# LED_Monitor.net
KiCad netlist of a schematic drawn in Altium Designer
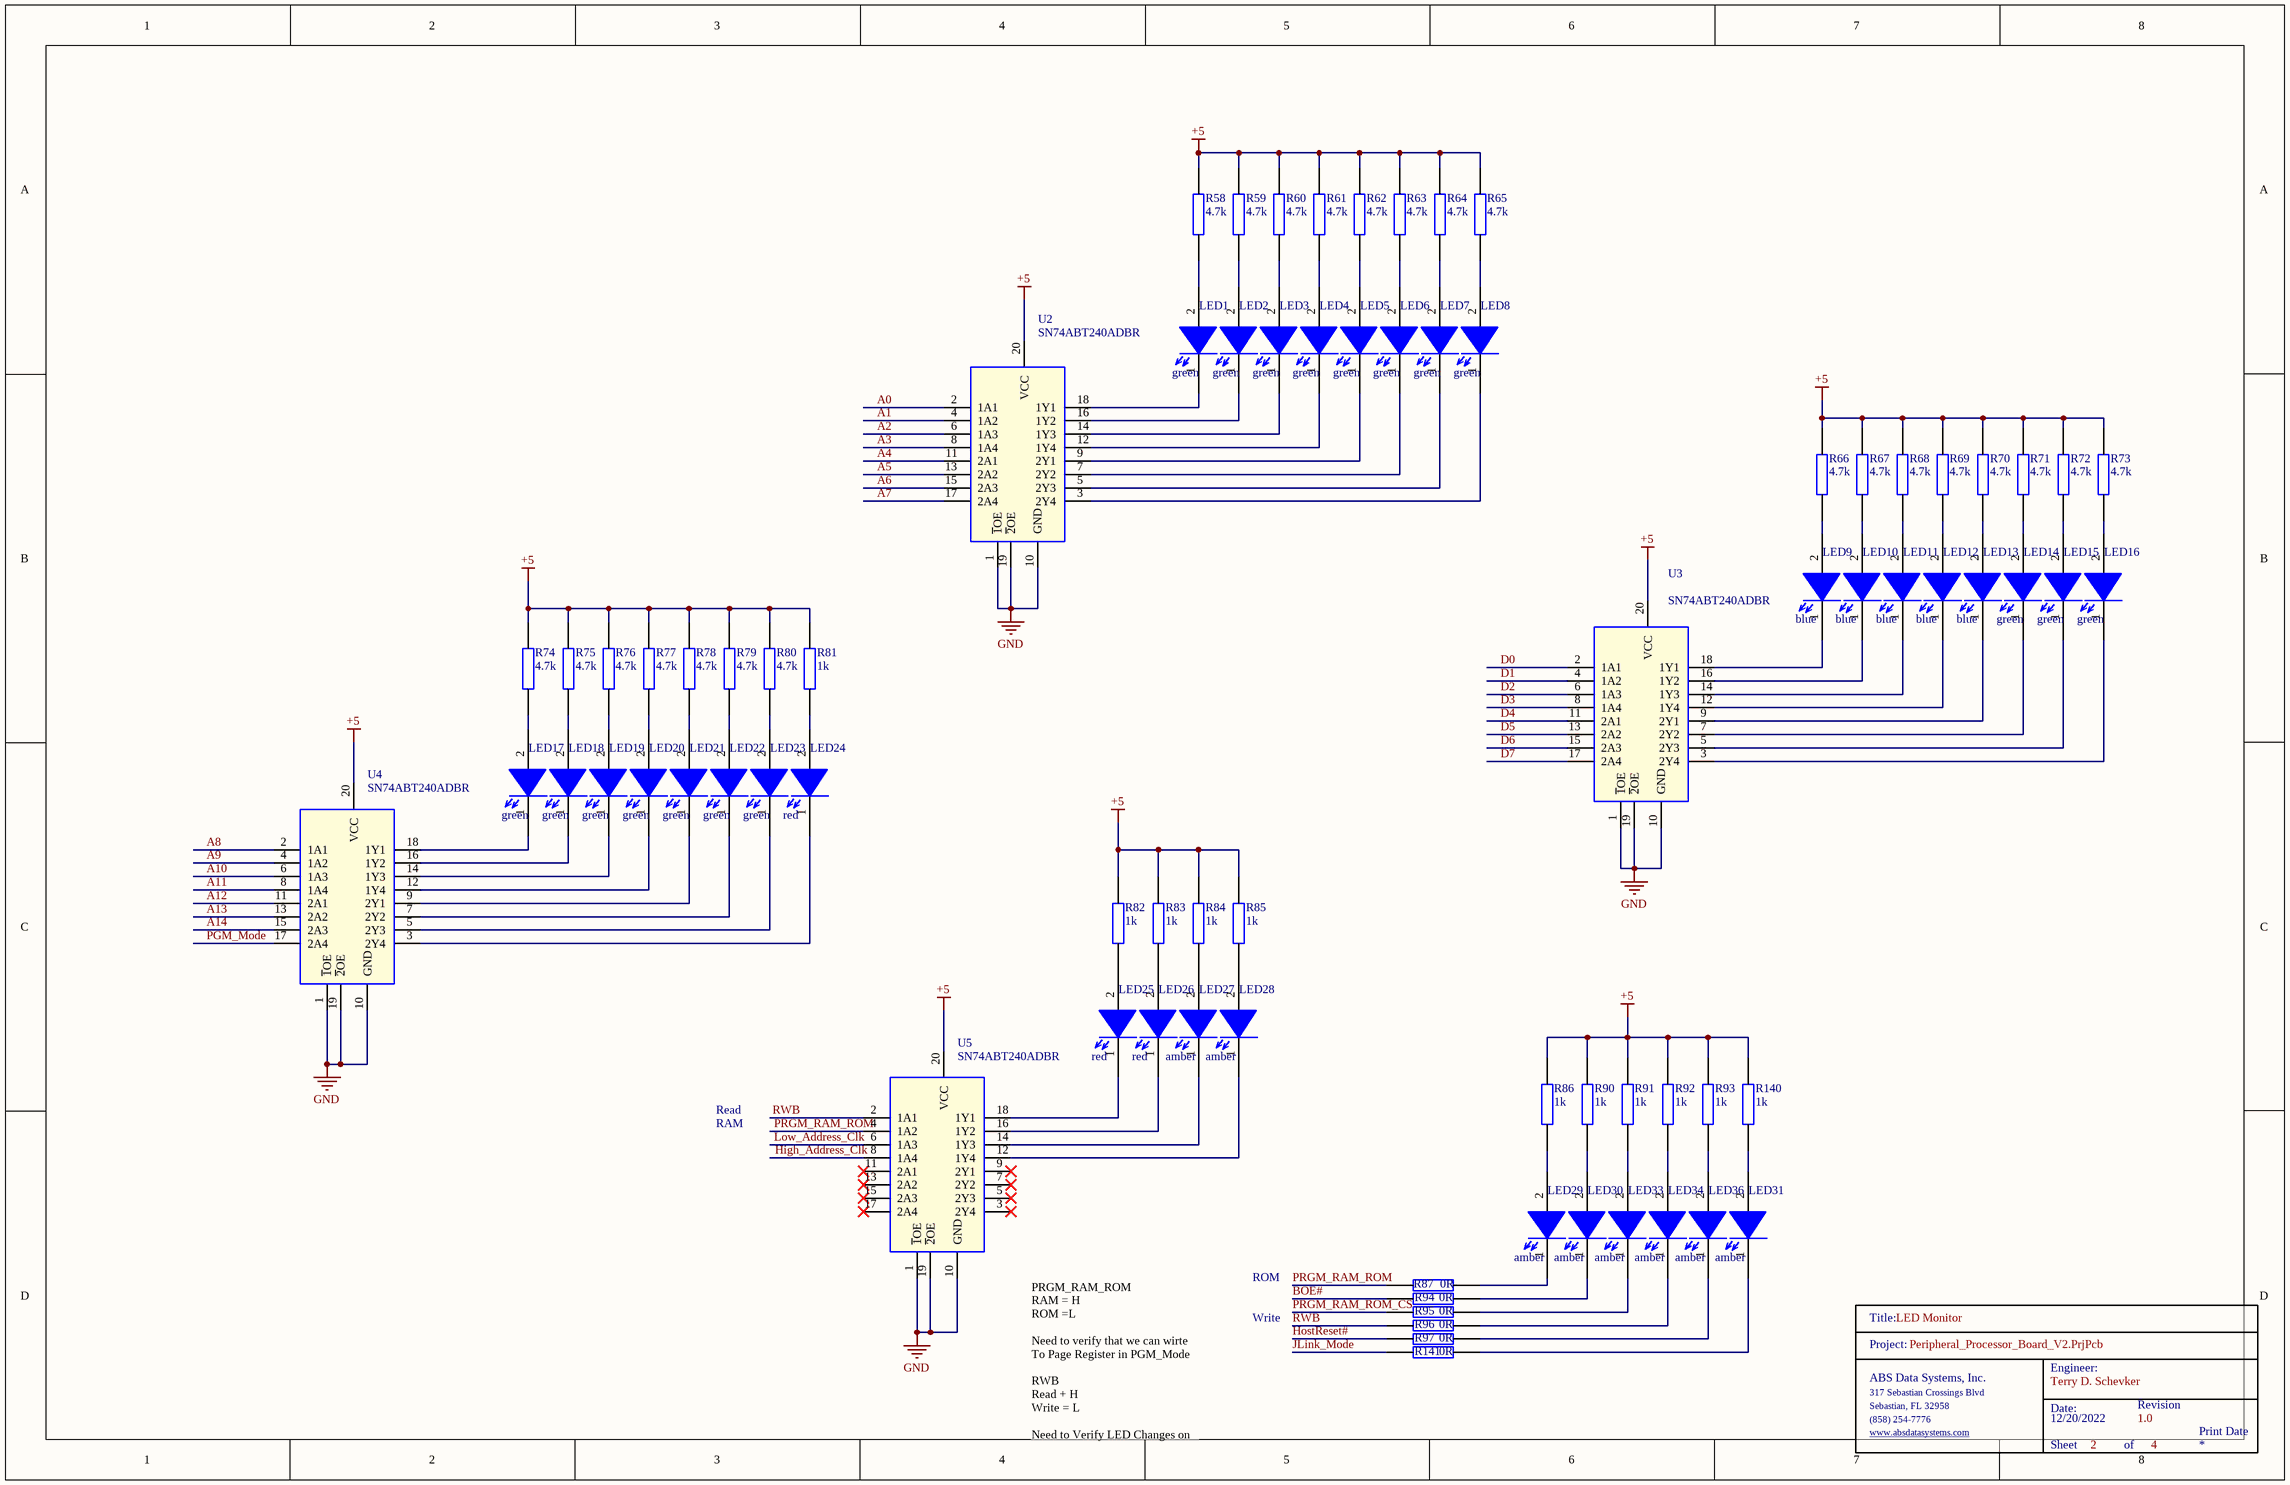
[diagram p0: LED_Monitor.SchDoc]

(export (version "E")
  (design (tool "Eeschema 10.0.6"))
  (components
    (comp (ref "LED1")
      (value "green")
      (footprint "0603_Diode")
      (description "Wurth Elektronik 0603 green")
      (fields
        (field (name "MANUFACTURER") "Wurth Electronics")
        (field (name "MANUFACTURER PART NUMBER") "150060GS75000")
      )
      (libsource (lib "Misc") (part "150060GS75000"))
    )
    (comp (ref "LED2")
      (value "green")
      (footprint "0603_Diode")
      (description "Wurth Elektronik 0603 green")
      (fields
        (field (name "MANUFACTURER") "Wurth Electronics")
        (field (name "MANUFACTURER PART NUMBER") "150060GS75000")
      )
      (libsource (lib "Misc") (part "150060GS75000"))
    )
    (comp (ref "LED3")
      (value "green")
      (footprint "0603_Diode")
      (description "Wurth Elektronik 0603 green")
      (fields
        (field (name "MANUFACTURER") "Wurth Electronics")
        (field (name "MANUFACTURER PART NUMBER") "150060GS75000")
      )
      (libsource (lib "Misc") (part "150060GS75000"))
    )
    (comp (ref "LED4")
      (value "green")
      (footprint "0603_Diode")
      (description "Wurth Elektronik 0603 green")
      (fields
        (field (name "MANUFACTURER") "Wurth Electronics")
        (field (name "MANUFACTURER PART NUMBER") "150060GS75000")
      )
      (libsource (lib "Misc") (part "150060GS75000"))
    )
    (comp (ref "LED5")
      (value "green")
      (footprint "0603_Diode")
      (description "Wurth Elektronik 0603 green")
      (fields
        (field (name "MANUFACTURER") "Wurth Electronics")
        (field (name "MANUFACTURER PART NUMBER") "150060GS75000")
      )
      (libsource (lib "Misc") (part "150060GS75000"))
    )
    (comp (ref "LED6")
      (value "green")
      (footprint "0603_Diode")
      (description "Wurth Elektronik 0603 green")
      (fields
        (field (name "MANUFACTURER") "Wurth Electronics")
        (field (name "MANUFACTURER PART NUMBER") "150060GS75000")
      )
      (libsource (lib "Misc") (part "150060GS75000"))
    )
    (comp (ref "LED7")
      (value "green")
      (footprint "0603_Diode")
      (description "Wurth Elektronik 0603 green")
      (fields
        (field (name "MANUFACTURER") "Wurth Electronics")
        (field (name "MANUFACTURER PART NUMBER") "150060GS75000")
      )
      (libsource (lib "Misc") (part "150060GS75000"))
    )
    (comp (ref "LED8")
      (value "green")
      (footprint "0603_Diode")
      (description "Wurth Elektronik 0603 green")
      (fields
        (field (name "MANUFACTURER") "Wurth Electronics")
        (field (name "MANUFACTURER PART NUMBER") "150060GS75000")
      )
      (libsource (lib "Misc") (part "150060GS75000"))
    )
    (comp (ref "LED9")
      (value "blue")
      (footprint "0603_Diode")
      (description "Wurth Elektronik 0603 blue")
      (fields
        (field (name "MANUFACTURER") "Wurth Electronics")
        (field (name "MANUFACTURER PART NUMBER") "150060GS75000")
      )
      (libsource (lib "Misc") (part "150060BS75000"))
    )
    (comp (ref "LED10")
      (value "blue")
      (footprint "0603_Diode")
      (description "Wurth Elektronik 0603 blue")
      (fields
        (field (name "MANUFACTURER") "Wurth Electronics")
        (field (name "MANUFACTURER PART NUMBER") "150060GS75000")
      )
      (libsource (lib "Misc") (part "150060BS75000"))
    )
    (comp (ref "LED11")
      (value "blue")
      (footprint "0603_Diode")
      (description "Wurth Elektronik 0603 blue")
      (fields
        (field (name "MANUFACTURER") "Wurth Electronics")
        (field (name "MANUFACTURER PART NUMBER") "150060GS75000")
      )
      (libsource (lib "Misc") (part "150060BS75000"))
    )
    (comp (ref "LED12")
      (value "blue")
      (footprint "0603_Diode")
      (description "Wurth Elektronik 0603 blue")
      (fields
        (field (name "MANUFACTURER") "Wurth Electronics")
        (field (name "MANUFACTURER PART NUMBER") "150060GS75000")
      )
      (libsource (lib "Misc") (part "150060BS75000"))
    )
    (comp (ref "LED13")
      (value "blue")
      (footprint "0603_Diode")
      (description "Wurth Elektronik 0603 blue")
      (fields
        (field (name "MANUFACTURER") "Wurth Electronics")
        (field (name "MANUFACTURER PART NUMBER") "150060GS75000")
      )
      (libsource (lib "Misc") (part "150060BS75000"))
    )
    (comp (ref "LED14")
      (value "green")
      (footprint "0603_Diode")
      (description "Wurth Elektronik 0603 green")
      (fields
        (field (name "MANUFACTURER") "Wurth Electronics")
        (field (name "MANUFACTURER PART NUMBER") "150060GS75000")
      )
      (libsource (lib "Misc") (part "150060GS75000"))
    )
    (comp (ref "LED15")
      (value "green")
      (footprint "0603_Diode")
      (description "Wurth Elektronik 0603 green")
      (fields
        (field (name "MANUFACTURER") "Wurth Electronics")
        (field (name "MANUFACTURER PART NUMBER") "150060GS75000")
      )
      (libsource (lib "Misc") (part "150060GS75000"))
    )
    (comp (ref "LED16")
      (value "green")
      (footprint "0603_Diode")
      (description "Wurth Elektronik 0603 green")
      (fields
        (field (name "MANUFACTURER") "Wurth Electronics")
        (field (name "MANUFACTURER PART NUMBER") "150060GS75000")
      )
      (libsource (lib "Misc") (part "150060GS75000"))
    )
    (comp (ref "LED17")
      (value "green")
      (footprint "0603_Diode")
      (description "Wurth Elektronik 0603 green")
      (fields
        (field (name "MANUFACTURER") "Wurth Electronics")
        (field (name "MANUFACTURER PART NUMBER") "150060GS75000")
      )
      (libsource (lib "Misc") (part "150060GS75000"))
    )
    (comp (ref "LED18")
      (value "green")
      (footprint "0603_Diode")
      (description "Wurth Elektronik 0603 green")
      (fields
        (field (name "MANUFACTURER") "Wurth Electronics")
        (field (name "MANUFACTURER PART NUMBER") "150060GS75000")
      )
      (libsource (lib "Misc") (part "150060GS75000"))
    )
    (comp (ref "LED19")
      (value "green")
      (footprint "0603_Diode")
      (description "Wurth Elektronik 0603 green")
      (fields
        (field (name "MANUFACTURER") "Wurth Electronics")
        (field (name "MANUFACTURER PART NUMBER") "150060GS75000")
      )
      (libsource (lib "Misc") (part "150060GS75000"))
    )
    (comp (ref "LED20")
      (value "green")
      (footprint "0603_Diode")
      (description "Wurth Elektronik 0603 green")
      (fields
        (field (name "MANUFACTURER") "Wurth Electronics")
        (field (name "MANUFACTURER PART NUMBER") "150060GS75000")
      )
      (libsource (lib "Misc") (part "150060GS75000"))
    )
    (comp (ref "LED21")
      (value "green")
      (footprint "0603_Diode")
      (description "Wurth Elektronik 0603 green")
      (fields
        (field (name "MANUFACTURER") "Wurth Electronics")
        (field (name "MANUFACTURER PART NUMBER") "150060GS75000")
      )
      (libsource (lib "Misc") (part "150060GS75000"))
    )
    (comp (ref "LED22")
      (value "green")
      (footprint "0603_Diode")
      (description "Wurth Elektronik 0603 green")
      (fields
        (field (name "MANUFACTURER") "Wurth Electronics")
        (field (name "MANUFACTURER PART NUMBER") "150060GS75000")
      )
      (libsource (lib "Misc") (part "150060GS75000"))
    )
    (comp (ref "LED23")
      (value "green")
      (footprint "0603_Diode")
      (description "Wurth Elektronik 0603 green")
      (fields
        (field (name "MANUFACTURER") "Wurth Electronics")
        (field (name "MANUFACTURER PART NUMBER") "150060GS75000")
      )
      (libsource (lib "Misc") (part "150060GS75000"))
    )
    (comp (ref "LED24")
      (value "red")
      (footprint "0603_Diode")
      (description "Wurth Elektronik 0603 red")
      (fields
        (field (name "MANUFACTURER") "Wurth Electronics")
        (field (name "MANUFACTURER PART NUMBER") "150060GS75000")
      )
      (libsource (lib "Misc") (part "150060RS75000"))
    )
    (comp (ref "LED25")
      (value "red")
      (footprint "0603_Diode")
      (description "Wurth Elektronik 0603 red")
      (fields
        (field (name "MANUFACTURER") "Wurth Electronics")
        (field (name "MANUFACTURER PART NUMBER") "150060GS75000")
      )
      (libsource (lib "Misc") (part "150060RS75000"))
    )
    (comp (ref "LED26")
      (value "red")
      (footprint "0603_Diode")
      (description "Wurth Elektronik 0603 red")
      (fields
        (field (name "MANUFACTURER") "Wurth Electronics")
        (field (name "MANUFACTURER PART NUMBER") "150060GS75000")
      )
      (libsource (lib "Misc") (part "150060RS75000"))
    )
    (comp (ref "LED27")
      (value "amber")
      (footprint "0603_Diode")
      (description "Wurth Elektronik 0603 amber")
      (fields
        (field (name "MANUFACTURER") "Wurth Electronics")
        (field (name "MANUFACTURER PART NUMBER") "150060GS75000")
      )
      (libsource (lib "Misc") (part "150060AS75000"))
    )
    (comp (ref "LED28")
      (value "amber")
      (footprint "0603_Diode")
      (description "Wurth Elektronik 0603 amber")
      (fields
        (field (name "MANUFACTURER") "Wurth Electronics")
        (field (name "MANUFACTURER PART NUMBER") "150060GS75000")
      )
      (libsource (lib "Misc") (part "150060AS75000"))
    )
    (comp (ref "LED29")
      (value "amber")
      (footprint "0603_Diode")
      (description "Wurth Elektronik 0603 amber")
      (fields
        (field (name "MANUFACTURER") "Wurth Electronics")
        (field (name "MANUFACTURER PART NUMBER") "150060GS75000")
      )
      (libsource (lib "Misc") (part "150060AS75000"))
    )
    (comp (ref "LED30")
      (value "amber")
      (footprint "0603_Diode")
      (description "Wurth Elektronik 0603 amber")
      (fields
        (field (name "MANUFACTURER") "Wurth Electronics")
        (field (name "MANUFACTURER PART NUMBER") "150060GS75000")
      )
      (libsource (lib "Misc") (part "150060AS75000"))
    )
    (comp (ref "LED31")
      (value "amber")
      (footprint "0603_Diode")
      (description "Wurth Elektronik 0603 amber")
      (fields
        (field (name "MANUFACTURER") "Wurth Electronics")
        (field (name "MANUFACTURER PART NUMBER") "150060GS75000")
      )
      (libsource (lib "Misc") (part "150060AS75000"))
    )
    (comp (ref "LED33")
      (value "amber")
      (footprint "0603_Diode")
      (description "Wurth Elektronik 0603 amber")
      (fields
        (field (name "MANUFACTURER") "Wurth Electronics")
        (field (name "MANUFACTURER PART NUMBER") "150060GS75000")
      )
      (libsource (lib "Misc") (part "150060AS75000"))
    )
    (comp (ref "LED34")
      (value "amber")
      (footprint "0603_Diode")
      (description "Wurth Elektronik 0603 amber")
      (fields
        (field (name "MANUFACTURER") "Wurth Electronics")
        (field (name "MANUFACTURER PART NUMBER") "150060GS75000")
      )
      (libsource (lib "Misc") (part "150060AS75000"))
    )
    (comp (ref "LED36")
      (value "amber")
      (footprint "0603_Diode")
      (description "Wurth Elektronik 0603 amber")
      (fields
        (field (name "MANUFACTURER") "Wurth Electronics")
        (field (name "MANUFACTURER PART NUMBER") "150060GS75000")
      )
      (libsource (lib "Misc") (part "150060AS75000"))
    )
    (comp (ref "R58")
      (value "4.7k")
      (footprint "0603")
      (description "YAGEO 0603 4.7k")
      (fields
        (field (name "MOUSER PART NUMBER") "603-RC0603JR-070RL")
        (field (name "MANUFACTURER_PART_NUMBER") "RC0603JR-070RL")
      )
      (libsource (lib "Resistors") (part "RC0603FR-104K7L"))
    )
    (comp (ref "R59")
      (value "4.7k")
      (footprint "0603")
      (description "YAGEO 0603 4.7k")
      (fields
        (field (name "MOUSER PART NUMBER") "603-RC0603JR-070RL")
        (field (name "MANUFACTURER_PART_NUMBER") "RC0603JR-070RL")
      )
      (libsource (lib "Resistors") (part "RC0603FR-104K7L"))
    )
    (comp (ref "R60")
      (value "4.7k")
      (footprint "0603")
      (description "YAGEO 0603 4.7k")
      (fields
        (field (name "MOUSER PART NUMBER") "603-RC0603JR-070RL")
        (field (name "MANUFACTURER_PART_NUMBER") "RC0603JR-070RL")
      )
      (libsource (lib "Resistors") (part "RC0603FR-104K7L"))
    )
    (comp (ref "R61")
      (value "4.7k")
      (footprint "0603")
      (description "YAGEO 0603 4.7k")
      (fields
        (field (name "MOUSER PART NUMBER") "603-RC0603JR-070RL")
        (field (name "MANUFACTURER_PART_NUMBER") "RC0603JR-070RL")
      )
      (libsource (lib "Resistors") (part "RC0603FR-104K7L"))
    )
    (comp (ref "R62")
      (value "4.7k")
      (footprint "0603")
      (description "YAGEO 0603 4.7k")
      (fields
        (field (name "MOUSER PART NUMBER") "603-RC0603JR-070RL")
        (field (name "MANUFACTURER_PART_NUMBER") "RC0603JR-070RL")
      )
      (libsource (lib "Resistors") (part "RC0603FR-104K7L"))
    )
    (comp (ref "R63")
      (value "4.7k")
      (footprint "0603")
      (description "YAGEO 0603 4.7k")
      (fields
        (field (name "MOUSER PART NUMBER") "603-RC0603JR-070RL")
        (field (name "MANUFACTURER_PART_NUMBER") "RC0603JR-070RL")
      )
      (libsource (lib "Resistors") (part "RC0603FR-104K7L"))
    )
    (comp (ref "R64")
      (value "4.7k")
      (footprint "0603")
      (description "YAGEO 0603 4.7k")
      (fields
        (field (name "MOUSER PART NUMBER") "603-RC0603JR-070RL")
        (field (name "MANUFACTURER_PART_NUMBER") "RC0603JR-070RL")
      )
      (libsource (lib "Resistors") (part "RC0603FR-104K7L"))
    )
    (comp (ref "R65")
      (value "4.7k")
      (footprint "0603")
      (description "YAGEO 0603 4.7k")
      (fields
        (field (name "MOUSER PART NUMBER") "603-RC0603JR-070RL")
        (field (name "MANUFACTURER_PART_NUMBER") "RC0603JR-070RL")
      )
      (libsource (lib "Resistors") (part "RC0603FR-104K7L"))
    )
    (comp (ref "R66")
      (value "4.7k")
      (footprint "0603")
      (description "YAGEO 0603 4.7k")
      (fields
        (field (name "MOUSER PART NUMBER") "603-RC0603JR-070RL")
        (field (name "MANUFACTURER_PART_NUMBER") "RC0603JR-070RL")
      )
      (libsource (lib "Resistors") (part "RC0603FR-104K7L"))
    )
    (comp (ref "R67")
      (value "4.7k")
      (footprint "0603")
      (description "YAGEO 0603 4.7k")
      (fields
        (field (name "MOUSER PART NUMBER") "603-RC0603JR-070RL")
        (field (name "MANUFACTURER_PART_NUMBER") "RC0603JR-070RL")
      )
      (libsource (lib "Resistors") (part "RC0603FR-104K7L"))
    )
    (comp (ref "R68")
      (value "4.7k")
      (footprint "0603")
      (description "YAGEO 0603 4.7k")
      (fields
        (field (name "MOUSER PART NUMBER") "603-RC0603JR-070RL")
        (field (name "MANUFACTURER_PART_NUMBER") "RC0603JR-070RL")
      )
      (libsource (lib "Resistors") (part "RC0603FR-104K7L"))
    )
    (comp (ref "R69")
      (value "4.7k")
      (footprint "0603")
      (description "YAGEO 0603 4.7k")
      (fields
        (field (name "MOUSER PART NUMBER") "603-RC0603JR-070RL")
        (field (name "MANUFACTURER_PART_NUMBER") "RC0603JR-070RL")
      )
      (libsource (lib "Resistors") (part "RC0603FR-104K7L"))
    )
    (comp (ref "R70")
      (value "4.7k")
      (footprint "0603")
      (description "YAGEO 0603 4.7k")
      (fields
        (field (name "MOUSER PART NUMBER") "603-RC0603JR-070RL")
        (field (name "MANUFACTURER_PART_NUMBER") "RC0603JR-070RL")
      )
      (libsource (lib "Resistors") (part "RC0603FR-104K7L"))
    )
    (comp (ref "R71")
      (value "4.7k")
      (footprint "0603")
      (description "YAGEO 0603 4.7k")
      (fields
        (field (name "MOUSER PART NUMBER") "603-RC0603JR-070RL")
        (field (name "MANUFACTURER_PART_NUMBER") "RC0603JR-070RL")
      )
      (libsource (lib "Resistors") (part "RC0603FR-104K7L"))
    )
    (comp (ref "R72")
      (value "4.7k")
      (footprint "0603")
      (description "YAGEO 0603 4.7k")
      (fields
        (field (name "MOUSER PART NUMBER") "603-RC0603JR-070RL")
        (field (name "MANUFACTURER_PART_NUMBER") "RC0603JR-070RL")
      )
      (libsource (lib "Resistors") (part "RC0603FR-104K7L"))
    )
    (comp (ref "R73")
      (value "4.7k")
      (footprint "0603")
      (description "YAGEO 0603 4.7k")
      (fields
        (field (name "MOUSER PART NUMBER") "603-RC0603JR-070RL")
        (field (name "MANUFACTURER_PART_NUMBER") "RC0603JR-070RL")
      )
      (libsource (lib "Resistors") (part "RC0603FR-104K7L"))
    )
    (comp (ref "R74")
      (value "4.7k")
      (footprint "0603")
      (description "YAGEO 0603 4.7k")
      (fields
        (field (name "MOUSER PART NUMBER") "603-RC0603JR-070RL")
        (field (name "MANUFACTURER_PART_NUMBER") "RC0603JR-070RL")
      )
      (libsource (lib "Resistors") (part "RC0603FR-104K7L"))
    )
    (comp (ref "R75")
      (value "4.7k")
      (footprint "0603")
      (description "YAGEO 0603 4.7k")
      (fields
        (field (name "MOUSER PART NUMBER") "603-RC0603JR-070RL")
        (field (name "MANUFACTURER_PART_NUMBER") "RC0603JR-070RL")
      )
      (libsource (lib "Resistors") (part "RC0603FR-104K7L"))
    )
    (comp (ref "R76")
      (value "4.7k")
      (footprint "0603")
      (description "YAGEO 0603 4.7k")
      (fields
        (field (name "MOUSER PART NUMBER") "603-RC0603JR-070RL")
        (field (name "MANUFACTURER_PART_NUMBER") "RC0603JR-070RL")
      )
      (libsource (lib "Resistors") (part "RC0603FR-104K7L"))
    )
    (comp (ref "R77")
      (value "4.7k")
      (footprint "0603")
      (description "YAGEO 0603 4.7k")
      (fields
        (field (name "MOUSER PART NUMBER") "603-RC0603JR-070RL")
        (field (name "MANUFACTURER_PART_NUMBER") "RC0603JR-070RL")
      )
      (libsource (lib "Resistors") (part "RC0603FR-104K7L"))
    )
    (comp (ref "R78")
      (value "4.7k")
      (footprint "0603")
      (description "YAGEO 0603 4.7k")
      (fields
        (field (name "MOUSER PART NUMBER") "603-RC0603JR-070RL")
        (field (name "MANUFACTURER_PART_NUMBER") "RC0603JR-070RL")
      )
      (libsource (lib "Resistors") (part "RC0603FR-104K7L"))
    )
    (comp (ref "R79")
      (value "4.7k")
      (footprint "0603")
      (description "YAGEO 0603 4.7k")
      (fields
        (field (name "MOUSER PART NUMBER") "603-RC0603JR-070RL")
        (field (name "MANUFACTURER_PART_NUMBER") "RC0603JR-070RL")
      )
      (libsource (lib "Resistors") (part "RC0603FR-104K7L"))
    )
    (comp (ref "R80")
      (value "4.7k")
      (footprint "0603")
      (description "YAGEO 0603 4.7k")
      (fields
        (field (name "MOUSER PART NUMBER") "603-RC0603JR-070RL")
        (field (name "MANUFACTURER_PART_NUMBER") "RC0603JR-070RL")
      )
      (libsource (lib "Resistors") (part "RC0603FR-104K7L"))
    )
    (comp (ref "R81")
      (value "1k")
      (footprint "0603")
      (description "YAGEO 0603 1k ohm")
      (fields
        (field (name "MOUSER PART NUMBER") "603-RC0603JR-070RL")
        (field (name "MANUFACTURER_PART_NUMBER") "RC0603JR-070RL")
      )
      (libsource (lib "Resistors") (part "AC0603FR-7W1KL_1"))
    )
    (comp (ref "R82")
      (value "1k")
      (footprint "0603")
      (description "YAGEO 0603 1k ohm")
      (fields
        (field (name "MOUSER PART NUMBER") "603-RC0603JR-070RL")
        (field (name "MANUFACTURER_PART_NUMBER") "RC0603JR-070RL")
      )
      (libsource (lib "Resistors") (part "AC0603FR-7W1KL_1"))
    )
    (comp (ref "R83")
      (value "1k")
      (footprint "0603")
      (description "YAGEO 0603 1k ohm")
      (fields
        (field (name "MOUSER PART NUMBER") "603-RC0603JR-070RL")
        (field (name "MANUFACTURER_PART_NUMBER") "RC0603JR-070RL")
      )
      (libsource (lib "Resistors") (part "AC0603FR-7W1KL_1"))
    )
    (comp (ref "R84")
      (value "1k")
      (footprint "0603")
      (description "YAGEO 0603 1k ohm")
      (fields
        (field (name "MOUSER PART NUMBER") "603-RC0603JR-070RL")
        (field (name "MANUFACTURER_PART_NUMBER") "RC0603JR-070RL")
      )
      (libsource (lib "Resistors") (part "AC0603FR-7W1KL_1"))
    )
    (comp (ref "R85")
      (value "1k")
      (footprint "0603")
      (description "YAGEO 0603 1k ohm")
      (fields
        (field (name "MOUSER PART NUMBER") "603-RC0603JR-070RL")
        (field (name "MANUFACTURER_PART_NUMBER") "RC0603JR-070RL")
      )
      (libsource (lib "Resistors") (part "AC0603FR-7W1KL_1"))
    )
    (comp (ref "R86")
      (value "1k")
      (footprint "0603")
      (description "YAGEO 0603 1k ohm")
      (fields
        (field (name "MOUSER PART NUMBER") "603-RC0603JR-070RL")
        (field (name "MANUFACTURER_PART_NUMBER") "RC0603JR-070RL")
      )
      (libsource (lib "Resistors") (part "AC0603FR-7W1KL_1"))
    )
    (comp (ref "R87")
      (value "0R")
      (footprint "0603")
      (description "YAGEO 0603 0 ohm")
      (fields
        (field (name "MOUSER PART NUMBER") "603-RC0603JR-070RL")
        (field (name "MANUFACTURER_PART_NUMBER") "RC0603JR-070RL")
      )
      (libsource (lib "Resistors") (part "RC0603JR-070RL"))
    )
    (comp (ref "R90")
      (value "1k")
      (footprint "0603")
      (description "YAGEO 0603 1k ohm")
      (fields
        (field (name "MOUSER PART NUMBER") "603-RC0603JR-070RL")
        (field (name "MANUFACTURER_PART_NUMBER") "RC0603JR-070RL")
      )
      (libsource (lib "Resistors") (part "AC0603FR-7W1KL_1"))
    )
    (comp (ref "R91")
      (value "1k")
      (footprint "0603")
      (description "YAGEO 0603 1k ohm")
      (fields
        (field (name "MOUSER PART NUMBER") "603-RC0603JR-070RL")
        (field (name "MANUFACTURER_PART_NUMBER") "RC0603JR-070RL")
      )
      (libsource (lib "Resistors") (part "AC0603FR-7W1KL_1"))
    )
    (comp (ref "R92")
      (value "1k")
      (footprint "0603")
      (description "YAGEO 0603 1k ohm")
      (fields
        (field (name "MOUSER PART NUMBER") "603-RC0603JR-070RL")
        (field (name "MANUFACTURER_PART_NUMBER") "RC0603JR-070RL")
      )
      (libsource (lib "Resistors") (part "AC0603FR-7W1KL_1"))
    )
    (comp (ref "R93")
      (value "1k")
      (footprint "0603")
      (description "YAGEO 0603 1k ohm")
      (fields
        (field (name "MOUSER PART NUMBER") "603-RC0603JR-070RL")
        (field (name "MANUFACTURER_PART_NUMBER") "RC0603JR-070RL")
      )
      (libsource (lib "Resistors") (part "AC0603FR-7W1KL_1"))
    )
    (comp (ref "R94")
      (value "0R")
      (footprint "0603")
      (description "YAGEO 0603 0 ohm")
      (fields
        (field (name "MOUSER PART NUMBER") "603-RC0603JR-070RL")
        (field (name "MANUFACTURER_PART_NUMBER") "RC0603JR-070RL")
      )
      (libsource (lib "Resistors") (part "RC0603JR-070RL"))
    )
    (comp (ref "R95")
      (value "0R")
      (footprint "0603")
      (description "YAGEO 0603 0 ohm")
      (fields
        (field (name "MOUSER PART NUMBER") "603-RC0603JR-070RL")
        (field (name "MANUFACTURER_PART_NUMBER") "RC0603JR-070RL")
      )
      (libsource (lib "Resistors") (part "RC0603JR-070RL"))
    )
    (comp (ref "R96")
      (value "0R")
      (footprint "0603")
      (description "YAGEO 0603 0 ohm")
      (fields
        (field (name "MOUSER PART NUMBER") "603-RC0603JR-070RL")
        (field (name "MANUFACTURER_PART_NUMBER") "RC0603JR-070RL")
      )
      (libsource (lib "Resistors") (part "RC0603JR-070RL"))
    )
    (comp (ref "R97")
      (value "0R")
      (footprint "0603")
      (description "YAGEO 0603 0 ohm")
      (fields
        (field (name "MOUSER PART NUMBER") "603-RC0603JR-070RL")
        (field (name "MANUFACTURER_PART_NUMBER") "RC0603JR-070RL")
      )
      (libsource (lib "Resistors") (part "RC0603JR-070RL"))
    )
    (comp (ref "R140")
      (value "1k")
      (footprint "Resistors:0603")
      (description "YAGEO 0603 1k ohm")
      (fields
        (field (name "MOUSER PART NUMBER") "603-RC0603JR-070RL")
        (field (name "MANUFACTURER_PART_NUMBER") "RC0603JR-070RL")
      )
      (libsource (lib "Resistors") (part "AC0603FR-7W1KL_1"))
    )
    (comp (ref "R141")
      (value "0R")
      (footprint "Resistors:0603")
      (description "YAGEO 0603 0 ohm")
      (fields
        (field (name "MOUSER PART NUMBER") "603-RC0603JR-070RL")
        (field (name "MANUFACTURER_PART_NUMBER") "RC0603JR-070RL")
      )
      (libsource (lib "Resistors") (part "RC0603JR-070RL"))
    )
    (comp (ref "TitleBlock_1") (value "TitleBlock") (libsource (lib "Misc") (part "TitleBlock")))
    (comp (ref "U2")
      (value "SN74ABT240ADBR")
      (footprint "SOP65P780X200-20N")
      (description "Octal Buffers/Drivers With 3-State Outputs")
      (fields (field (name "MOUSER PART NUMBER") "595-SN74ABT240ADBR"))
      (libsource (lib "Logic") (part "SN74ABT240ADBR"))
    )
    (comp (ref "U3")
      (value "SN74ABT240ADBR")
      (footprint "SOP65P780X200-20N")
      (description "Octal Buffers/Drivers With 3-State Outputs")
      (fields (field (name "MOUSER PART NUMBER") "595-SN74ABT240ADBR"))
      (libsource (lib "Logic") (part "SN74ABT240ADBR"))
    )
    (comp (ref "U4")
      (value "SN74ABT240ADBR")
      (footprint "SOP65P780X200-20N")
      (description "Octal Buffers/Drivers With 3-State Outputs")
      (fields (field (name "MOUSER PART NUMBER") "595-SN74ABT240ADBR"))
      (libsource (lib "Logic") (part "SN74ABT240ADBR"))
    )
    (comp (ref "U5")
      (value "SN74ABT240ADBR")
      (footprint "SOP65P780X200-20N")
      (description "Octal Buffers/Drivers With 3-State Outputs")
      (fields (field (name "MOUSER PART NUMBER") "595-SN74ABT240ADBR"))
      (libsource (lib "Logic") (part "SN74ABT240ADBR"))
    )
  )
  (nets
    (net (code "1") (name "+5") (class "Default")
      (node (ref "R140") (pin "2") (pinfunction "2_2") (pintype "passive"))
      (node (ref "R58") (pin "2") (pinfunction "2_2") (pintype "passive"))
      (node (ref "R59") (pin "2") (pinfunction "2_2") (pintype "passive"))
      (node (ref "R60") (pin "2") (pinfunction "2_2") (pintype "passive"))
      (node (ref "R61") (pin "2") (pinfunction "2_2") (pintype "passive"))
      (node (ref "R62") (pin "2") (pinfunction "2_2") (pintype "passive"))
      (node (ref "R63") (pin "2") (pinfunction "2_2") (pintype "passive"))
      (node (ref "R64") (pin "2") (pinfunction "2_2") (pintype "passive"))
      (node (ref "R65") (pin "2") (pinfunction "2_2") (pintype "passive"))
      (node (ref "R66") (pin "2") (pinfunction "2_2") (pintype "passive"))
      (node (ref "R67") (pin "2") (pinfunction "2_2") (pintype "passive"))
      (node (ref "R68") (pin "2") (pinfunction "2_2") (pintype "passive"))
      (node (ref "R69") (pin "2") (pinfunction "2_2") (pintype "passive"))
      (node (ref "R70") (pin "2") (pinfunction "2_2") (pintype "passive"))
      (node (ref "R71") (pin "2") (pinfunction "2_2") (pintype "passive"))
      (node (ref "R72") (pin "2") (pinfunction "2_2") (pintype "passive"))
      (node (ref "R73") (pin "2") (pinfunction "2_2") (pintype "passive"))
      (node (ref "R74") (pin "2") (pinfunction "2_2") (pintype "passive"))
      (node (ref "R75") (pin "2") (pinfunction "2_2") (pintype "passive"))
      (node (ref "R76") (pin "2") (pinfunction "2_2") (pintype "passive"))
      (node (ref "R77") (pin "2") (pinfunction "2_2") (pintype "passive"))
      (node (ref "R78") (pin "2") (pinfunction "2_2") (pintype "passive"))
      (node (ref "R79") (pin "2") (pinfunction "2_2") (pintype "passive"))
      (node (ref "R80") (pin "2") (pinfunction "2_2") (pintype "passive"))
      (node (ref "R81") (pin "2") (pinfunction "2_2") (pintype "passive"))
      (node (ref "R82") (pin "2") (pinfunction "2_2") (pintype "passive"))
      (node (ref "R83") (pin "2") (pinfunction "2_2") (pintype "passive"))
      (node (ref "R84") (pin "2") (pinfunction "2_2") (pintype "passive"))
      (node (ref "R85") (pin "2") (pinfunction "2_2") (pintype "passive"))
      (node (ref "R86") (pin "2") (pinfunction "2_2") (pintype "passive"))
      (node (ref "R90") (pin "2") (pinfunction "2_2") (pintype "passive"))
      (node (ref "R91") (pin "2") (pinfunction "2_2") (pintype "passive"))
      (node (ref "R92") (pin "2") (pinfunction "2_2") (pintype "passive"))
      (node (ref "R93") (pin "2") (pinfunction "2_2") (pintype "passive"))
      (node (ref "U2") (pin "20") (pinfunction "VCC_20") (pintype "passive"))
      (node (ref "U3") (pin "20") (pinfunction "VCC_20") (pintype "passive"))
      (node (ref "U4") (pin "20") (pinfunction "VCC_20") (pintype "passive"))
      (node (ref "U5") (pin "20") (pinfunction "VCC_20") (pintype "passive"))
    )
    (net (code "2") (name "/A0") (class "Default")
      (node (ref "U2") (pin "2") (pinfunction "1A1_2") (pintype "passive"))
    )
    (net (code "3") (name "/A1") (class "Default")
      (node (ref "U2") (pin "4") (pinfunction "1A2_4") (pintype "passive"))
    )
    (net (code "4") (name "/A2") (class "Default")
      (node (ref "U2") (pin "6") (pinfunction "1A3_6") (pintype "passive"))
    )
    (net (code "5") (name "/A3") (class "Default")
      (node (ref "U2") (pin "8") (pinfunction "1A4_8") (pintype "passive"))
    )
    (net (code "6") (name "/A4") (class "Default")
      (node (ref "U2") (pin "11") (pinfunction "2A1_11") (pintype "passive"))
    )
    (net (code "7") (name "/A5") (class "Default")
      (node (ref "U2") (pin "13") (pinfunction "2A2_13") (pintype "passive"))
    )
    (net (code "8") (name "/A6") (class "Default")
      (node (ref "U2") (pin "15") (pinfunction "2A3_15") (pintype "passive"))
    )
    (net (code "9") (name "/A7") (class "Default")
      (node (ref "U2") (pin "17") (pinfunction "2A4_17") (pintype "passive"))
    )
    (net (code "10") (name "/A8") (class "Default")
      (node (ref "U4") (pin "2") (pinfunction "1A1_2") (pintype "passive"))
    )
    (net (code "11") (name "/A9") (class "Default")
      (node (ref "U4") (pin "4") (pinfunction "1A2_4") (pintype "passive"))
    )
    (net (code "12") (name "/A10") (class "Default")
      (node (ref "U4") (pin "6") (pinfunction "1A3_6") (pintype "passive"))
    )
    (net (code "13") (name "/A11") (class "Default")
      (node (ref "U4") (pin "8") (pinfunction "1A4_8") (pintype "passive"))
    )
    (net (code "14") (name "/A12") (class "Default")
      (node (ref "U4") (pin "11") (pinfunction "2A1_11") (pintype "passive"))
    )
    (net (code "15") (name "/A13") (class "Default")
      (node (ref "U4") (pin "13") (pinfunction "2A2_13") (pintype "passive"))
    )
    (net (code "16") (name "/A14") (class "Default")
      (node (ref "U4") (pin "15") (pinfunction "2A3_15") (pintype "passive"))
    )
    (net (code "17") (name "/BOE#") (class "Default")
      (node (ref "R94") (pin "1") (pinfunction "1_1") (pintype "passive"))
    )
    (net (code "18") (name "/D0") (class "Default")
      (node (ref "U3") (pin "2") (pinfunction "1A1_2") (pintype "passive"))
    )
    (net (code "19") (name "/D1") (class "Default")
      (node (ref "U3") (pin "4") (pinfunction "1A2_4") (pintype "passive"))
    )
    (net (code "20") (name "/D2") (class "Default")
      (node (ref "U3") (pin "6") (pinfunction "1A3_6") (pintype "passive"))
    )
    (net (code "21") (name "/D3") (class "Default")
      (node (ref "U3") (pin "8") (pinfunction "1A4_8") (pintype "passive"))
    )
    (net (code "22") (name "/D4") (class "Default")
      (node (ref "U3") (pin "11") (pinfunction "2A1_11") (pintype "passive"))
    )
    (net (code "23") (name "/D5") (class "Default")
      (node (ref "U3") (pin "13") (pinfunction "2A2_13") (pintype "passive"))
    )
    (net (code "24") (name "/D6") (class "Default")
      (node (ref "U3") (pin "15") (pinfunction "2A3_15") (pintype "passive"))
    )
    (net (code "25") (name "/D7") (class "Default")
      (node (ref "U3") (pin "17") (pinfunction "2A4_17") (pintype "passive"))
    )
    (net (code "26") (name "/High_Address_Clk") (class "Default")
      (node (ref "U5") (pin "8") (pinfunction "1A4_8") (pintype "passive"))
    )
    (net (code "27") (name "/HostReset#") (class "Default")
      (node (ref "R97") (pin "1") (pinfunction "1_1") (pintype "passive"))
    )
    (net (code "28") (name "/JLink_Mode") (class "Default")
      (node (ref "R141") (pin "1") (pinfunction "1_1") (pintype "passive"))
    )
    (net (code "29") (name "/Low_Address_Clk") (class "Default")
      (node (ref "U5") (pin "6") (pinfunction "1A3_6") (pintype "passive"))
    )
    (net (code "30") (name "/PGM_Mode") (class "Default")
      (node (ref "U4") (pin "17") (pinfunction "2A4_17") (pintype "passive"))
    )
    (net (code "31") (name "/PRGM_RAM_ROM") (class "Default")
      (node (ref "R87") (pin "1") (pinfunction "1_1") (pintype "passive"))
      (node (ref "U5") (pin "4") (pinfunction "1A2_4") (pintype "passive"))
    )
    (net (code "32") (name "/PRGM_RAM_ROM_CS") (class "Default")
      (node (ref "R95") (pin "1") (pinfunction "1_1") (pintype "passive"))
    )
    (net (code "33") (name "/RWB") (class "Default")
      (node (ref "R96") (pin "1") (pinfunction "1_1") (pintype "passive"))
      (node (ref "U5") (pin "2") (pinfunction "1A1_2") (pintype "passive"))
    )
    (net (code "34") (name "GND") (class "Default")
      (node (ref "U2") (pin "1") (pinfunction "~{1}OE_1") (pintype "passive"))
      (node (ref "U2") (pin "10") (pinfunction "GND_10") (pintype "passive"))
      (node (ref "U2") (pin "19") (pinfunction "~{2}OE_19") (pintype "passive"))
      (node (ref "U3") (pin "1") (pinfunction "~{1}OE_1") (pintype "passive"))
      (node (ref "U3") (pin "10") (pinfunction "GND_10") (pintype "passive"))
      (node (ref "U3") (pin "19") (pinfunction "~{2}OE_19") (pintype "passive"))
      (node (ref "U4") (pin "1") (pinfunction "~{1}OE_1") (pintype "passive"))
      (node (ref "U4") (pin "10") (pinfunction "GND_10") (pintype "passive"))
      (node (ref "U4") (pin "19") (pinfunction "~{2}OE_19") (pintype "passive"))
      (node (ref "U5") (pin "1") (pinfunction "~{1}OE_1") (pintype "passive"))
      (node (ref "U5") (pin "10") (pinfunction "GND_10") (pintype "passive"))
      (node (ref "U5") (pin "19") (pinfunction "~{2}OE_19") (pintype "passive"))
    )
    (net (code "35") (name "Net-(LED1-A)") (class "Default")
      (node (ref "LED1") (pin "2") (pinfunction "A_2") (pintype "passive"))
      (node (ref "R58") (pin "1") (pinfunction "1_1") (pintype "passive"))
    )
    (net (code "36") (name "Net-(LED1-K)") (class "Default")
      (node (ref "LED1") (pin "1") (pinfunction "K_1") (pintype "passive"))
      (node (ref "U2") (pin "18") (pinfunction "1Y1_18") (pintype "passive"))
    )
    (net (code "37") (name "Net-(LED2-A)") (class "Default")
      (node (ref "LED2") (pin "2") (pinfunction "A_2") (pintype "passive"))
      (node (ref "R59") (pin "1") (pinfunction "1_1") (pintype "passive"))
    )
    (net (code "38") (name "Net-(LED2-K)") (class "Default")
      (node (ref "LED2") (pin "1") (pinfunction "K_1") (pintype "passive"))
      (node (ref "U2") (pin "16") (pinfunction "1Y2_16") (pintype "passive"))
    )
    (net (code "39") (name "Net-(LED3-A)") (class "Default")
      (node (ref "LED3") (pin "2") (pinfunction "A_2") (pintype "passive"))
      (node (ref "R60") (pin "1") (pinfunction "1_1") (pintype "passive"))
    )
    (net (code "40") (name "Net-(LED3-K)") (class "Default")
      (node (ref "LED3") (pin "1") (pinfunction "K_1") (pintype "passive"))
      (node (ref "U2") (pin "14") (pinfunction "1Y3_14") (pintype "passive"))
    )
    (net (code "41") (name "Net-(LED4-A)") (class "Default")
      (node (ref "LED4") (pin "2") (pinfunction "A_2") (pintype "passive"))
      (node (ref "R61") (pin "1") (pinfunction "1_1") (pintype "passive"))
    )
    (net (code "42") (name "Net-(LED4-K)") (class "Default")
      (node (ref "LED4") (pin "1") (pinfunction "K_1") (pintype "passive"))
      (node (ref "U2") (pin "12") (pinfunction "1Y4_12") (pintype "passive"))
    )
    (net (code "43") (name "Net-(LED5-A)") (class "Default")
      (node (ref "LED5") (pin "2") (pinfunction "A_2") (pintype "passive"))
      (node (ref "R62") (pin "1") (pinfunction "1_1") (pintype "passive"))
    )
    (net (code "44") (name "Net-(LED5-K)") (class "Default")
      (node (ref "LED5") (pin "1") (pinfunction "K_1") (pintype "passive"))
      (node (ref "U2") (pin "9") (pinfunction "2Y1_9") (pintype "passive"))
    )
    (net (code "45") (name "Net-(LED6-A)") (class "Default")
      (node (ref "LED6") (pin "2") (pinfunction "A_2") (pintype "passive"))
      (node (ref "R63") (pin "1") (pinfunction "1_1") (pintype "passive"))
    )
    (net (code "46") (name "Net-(LED6-K)") (class "Default")
      (node (ref "LED6") (pin "1") (pinfunction "K_1") (pintype "passive"))
      (node (ref "U2") (pin "7") (pinfunction "2Y2_7") (pintype "passive"))
    )
    (net (code "47") (name "Net-(LED7-A)") (class "Default")
      (node (ref "LED7") (pin "2") (pinfunction "A_2") (pintype "passive"))
      (node (ref "R64") (pin "1") (pinfunction "1_1") (pintype "passive"))
    )
    (net (code "48") (name "Net-(LED7-K)") (class "Default")
      (node (ref "LED7") (pin "1") (pinfunction "K_1") (pintype "passive"))
      (node (ref "U2") (pin "5") (pinfunction "2Y3_5") (pintype "passive"))
    )
    (net (code "49") (name "Net-(LED8-A)") (class "Default")
      (node (ref "LED8") (pin "2") (pinfunction "A_2") (pintype "passive"))
      (node (ref "R65") (pin "1") (pinfunction "1_1") (pintype "passive"))
    )
    (net (code "50") (name "Net-(LED8-K)") (class "Default")
      (node (ref "LED8") (pin "1") (pinfunction "K_1") (pintype "passive"))
      (node (ref "U2") (pin "3") (pinfunction "2Y4_3") (pintype "passive"))
    )
    (net (code "51") (name "Net-(LED9-A)") (class "Default")
      (node (ref "LED9") (pin "2") (pinfunction "A_2") (pintype "passive"))
      (node (ref "R66") (pin "1") (pinfunction "1_1") (pintype "passive"))
    )
    (net (code "52") (name "Net-(LED9-K)") (class "Default")
      (node (ref "LED9") (pin "1") (pinfunction "K_1") (pintype "passive"))
      (node (ref "U3") (pin "18") (pinfunction "1Y1_18") (pintype "passive"))
    )
    (net (code "53") (name "Net-(LED10-A)") (class "Default")
      (node (ref "LED10") (pin "2") (pinfunction "A_2") (pintype "passive"))
      (node (ref "R67") (pin "1") (pinfunction "1_1") (pintype "passive"))
    )
    (net (code "54") (name "Net-(LED10-K)") (class "Default")
      (node (ref "LED10") (pin "1") (pinfunction "K_1") (pintype "passive"))
      (node (ref "U3") (pin "16") (pinfunction "1Y2_16") (pintype "passive"))
    )
    (net (code "55") (name "Net-(LED11-A)") (class "Default")
      (node (ref "LED11") (pin "2") (pinfunction "A_2") (pintype "passive"))
      (node (ref "R68") (pin "1") (pinfunction "1_1") (pintype "passive"))
    )
    (net (code "56") (name "Net-(LED11-K)") (class "Default")
      (node (ref "LED11") (pin "1") (pinfunction "K_1") (pintype "passive"))
      (node (ref "U3") (pin "14") (pinfunction "1Y3_14") (pintype "passive"))
    )
    (net (code "57") (name "Net-(LED12-A)") (class "Default")
      (node (ref "LED12") (pin "2") (pinfunction "A_2") (pintype "passive"))
      (node (ref "R69") (pin "1") (pinfunction "1_1") (pintype "passive"))
    )
    (net (code "58") (name "Net-(LED12-K)") (class "Default")
      (node (ref "LED12") (pin "1") (pinfunction "K_1") (pintype "passive"))
      (node (ref "U3") (pin "12") (pinfunction "1Y4_12") (pintype "passive"))
    )
    (net (code "59") (name "Net-(LED13-A)") (class "Default")
      (node (ref "LED13") (pin "2") (pinfunction "A_2") (pintype "passive"))
      (node (ref "R70") (pin "1") (pinfunction "1_1") (pintype "passive"))
    )
    (net (code "60") (name "Net-(LED13-K)") (class "Default")
      (node (ref "LED13") (pin "1") (pinfunction "K_1") (pintype "passive"))
      (node (ref "U3") (pin "9") (pinfunction "2Y1_9") (pintype "passive"))
    )
    (net (code "61") (name "Net-(LED14-A)") (class "Default")
      (node (ref "LED14") (pin "2") (pinfunction "A_2") (pintype "passive"))
      (node (ref "R71") (pin "1") (pinfunction "1_1") (pintype "passive"))
    )
    (net (code "62") (name "Net-(LED14-K)") (class "Default")
      (node (ref "LED14") (pin "1") (pinfunction "K_1") (pintype "passive"))
      (node (ref "U3") (pin "7") (pinfunction "2Y2_7") (pintype "passive"))
    )
    (net (code "63") (name "Net-(LED15-A)") (class "Default")
      (node (ref "LED15") (pin "2") (pinfunction "A_2") (pintype "passive"))
      (node (ref "R72") (pin "1") (pinfunction "1_1") (pintype "passive"))
    )
    (net (code "64") (name "Net-(LED15-K)") (class "Default")
      (node (ref "LED15") (pin "1") (pinfunction "K_1") (pintype "passive"))
      (node (ref "U3") (pin "5") (pinfunction "2Y3_5") (pintype "passive"))
    )
    (net (code "65") (name "Net-(LED16-A)") (class "Default")
      (node (ref "LED16") (pin "2") (pinfunction "A_2") (pintype "passive"))
      (node (ref "R73") (pin "1") (pinfunction "1_1") (pintype "passive"))
    )
    (net (code "66") (name "Net-(LED16-K)") (class "Default")
      (node (ref "LED16") (pin "1") (pinfunction "K_1") (pintype "passive"))
      (node (ref "U3") (pin "3") (pinfunction "2Y4_3") (pintype "passive"))
    )
    (net (code "67") (name "Net-(LED17-A)") (class "Default")
      (node (ref "LED17") (pin "2") (pinfunction "A_2") (pintype "passive"))
      (node (ref "R74") (pin "1") (pinfunction "1_1") (pintype "passive"))
    )
    (net (code "68") (name "Net-(LED17-K)") (class "Default")
      (node (ref "LED17") (pin "1") (pinfunction "K_1") (pintype "passive"))
      (node (ref "U4") (pin "18") (pinfunction "1Y1_18") (pintype "passive"))
    )
    (net (code "69") (name "Net-(LED18-A)") (class "Default")
      (node (ref "LED18") (pin "2") (pinfunction "A_2") (pintype "passive"))
      (node (ref "R75") (pin "1") (pinfunction "1_1") (pintype "passive"))
    )
    (net (code "70") (name "Net-(LED18-K)") (class "Default")
      (node (ref "LED18") (pin "1") (pinfunction "K_1") (pintype "passive"))
      (node (ref "U4") (pin "16") (pinfunction "1Y2_16") (pintype "passive"))
    )
    (net (code "71") (name "Net-(LED19-A)") (class "Default")
      (node (ref "LED19") (pin "2") (pinfunction "A_2") (pintype "passive"))
      (node (ref "R76") (pin "1") (pinfunction "1_1") (pintype "passive"))
    )
    (net (code "72") (name "Net-(LED19-K)") (class "Default")
      (node (ref "LED19") (pin "1") (pinfunction "K_1") (pintype "passive"))
      (node (ref "U4") (pin "14") (pinfunction "1Y3_14") (pintype "passive"))
    )
    (net (code "73") (name "Net-(LED20-A)") (class "Default")
      (node (ref "LED20") (pin "2") (pinfunction "A_2") (pintype "passive"))
      (node (ref "R77") (pin "1") (pinfunction "1_1") (pintype "passive"))
    )
    (net (code "74") (name "Net-(LED20-K)") (class "Default")
      (node (ref "LED20") (pin "1") (pinfunction "K_1") (pintype "passive"))
      (node (ref "U4") (pin "12") (pinfunction "1Y4_12") (pintype "passive"))
    )
    (net (code "75") (name "Net-(LED21-A)") (class "Default")
      (node (ref "LED21") (pin "2") (pinfunction "A_2") (pintype "passive"))
      (node (ref "R78") (pin "1") (pinfunction "1_1") (pintype "passive"))
    )
    (net (code "76") (name "Net-(LED21-K)") (class "Default")
      (node (ref "LED21") (pin "1") (pinfunction "K_1") (pintype "passive"))
      (node (ref "U4") (pin "9") (pinfunction "2Y1_9") (pintype "passive"))
    )
    (net (code "77") (name "Net-(LED22-A)") (class "Default")
      (node (ref "LED22") (pin "2") (pinfunction "A_2") (pintype "passive"))
      (node (ref "R79") (pin "1") (pinfunction "1_1") (pintype "passive"))
    )
    (net (code "78") (name "Net-(LED22-K)") (class "Default")
      (node (ref "LED22") (pin "1") (pinfunction "K_1") (pintype "passive"))
      (node (ref "U4") (pin "7") (pinfunction "2Y2_7") (pintype "passive"))
    )
    (net (code "79") (name "Net-(LED23-A)") (class "Default")
      (node (ref "LED23") (pin "2") (pinfunction "A_2") (pintype "passive"))
      (node (ref "R80") (pin "1") (pinfunction "1_1") (pintype "passive"))
    )
    (net (code "80") (name "Net-(LED23-K)") (class "Default")
      (node (ref "LED23") (pin "1") (pinfunction "K_1") (pintype "passive"))
      (node (ref "U4") (pin "5") (pinfunction "2Y3_5") (pintype "passive"))
    )
    (net (code "81") (name "Net-(LED24-A)") (class "Default")
      (node (ref "LED24") (pin "2") (pinfunction "A_2") (pintype "passive"))
      (node (ref "R81") (pin "1") (pinfunction "1_1") (pintype "passive"))
    )
    (net (code "82") (name "Net-(LED24-K)") (class "Default")
      (node (ref "LED24") (pin "1") (pinfunction "K_1") (pintype "passive"))
      (node (ref "U4") (pin "3") (pinfunction "2Y4_3") (pintype "passive"))
    )
    (net (code "83") (name "Net-(LED25-A)") (class "Default")
      (node (ref "LED25") (pin "2") (pinfunction "A_2") (pintype "passive"))
      (node (ref "R82") (pin "1") (pinfunction "1_1") (pintype "passive"))
    )
    (net (code "84") (name "Net-(LED25-K)") (class "Default")
      (node (ref "LED25") (pin "1") (pinfunction "K_1") (pintype "passive"))
      (node (ref "U5") (pin "18") (pinfunction "1Y1_18") (pintype "passive"))
    )
    (net (code "85") (name "Net-(LED26-A)") (class "Default")
      (node (ref "LED26") (pin "2") (pinfunction "A_2") (pintype "passive"))
      (node (ref "R83") (pin "1") (pinfunction "1_1") (pintype "passive"))
    )
    (net (code "86") (name "Net-(LED26-K)") (class "Default")
      (node (ref "LED26") (pin "1") (pinfunction "K_1") (pintype "passive"))
      (node (ref "U5") (pin "16") (pinfunction "1Y2_16") (pintype "passive"))
    )
    (net (code "87") (name "Net-(LED27-A)") (class "Default")
      (node (ref "LED27") (pin "2") (pinfunction "A_2") (pintype "passive"))
      (node (ref "R84") (pin "1") (pinfunction "1_1") (pintype "passive"))
    )
    (net (code "88") (name "Net-(LED27-K)") (class "Default")
      (node (ref "LED27") (pin "1") (pinfunction "K_1") (pintype "passive"))
      (node (ref "U5") (pin "14") (pinfunction "1Y3_14") (pintype "passive"))
    )
    (net (code "89") (name "Net-(LED28-A)") (class "Default")
      (node (ref "LED28") (pin "2") (pinfunction "A_2") (pintype "passive"))
      (node (ref "R85") (pin "1") (pinfunction "1_1") (pintype "passive"))
    )
    (net (code "90") (name "Net-(LED28-K)") (class "Default")
      (node (ref "LED28") (pin "1") (pinfunction "K_1") (pintype "passive"))
      (node (ref "U5") (pin "12") (pinfunction "1Y4_12") (pintype "passive"))
    )
    (net (code "91") (name "Net-(LED29-A)") (class "Default")
      (node (ref "LED29") (pin "2") (pinfunction "A_2") (pintype "passive"))
      (node (ref "R86") (pin "1") (pinfunction "1_1") (pintype "passive"))
    )
    (net (code "92") (name "Net-(LED29-K)") (class "Default")
      (node (ref "LED29") (pin "1") (pinfunction "K_1") (pintype "passive"))
      (node (ref "R87") (pin "2") (pinfunction "2_2") (pintype "passive"))
    )
    (net (code "93") (name "Net-(LED30-A)") (class "Default")
      (node (ref "LED30") (pin "2") (pinfunction "A_2") (pintype "passive"))
      (node (ref "R90") (pin "1") (pinfunction "1_1") (pintype "passive"))
    )
    (net (code "94") (name "Net-(LED30-K)") (class "Default")
      (node (ref "LED30") (pin "1") (pinfunction "K_1") (pintype "passive"))
      (node (ref "R94") (pin "2") (pinfunction "2_2") (pintype "passive"))
    )
    (net (code "95") (name "Net-(LED31-A)") (class "Default")
      (node (ref "LED31") (pin "2") (pinfunction "A_2") (pintype "passive"))
      (node (ref "R140") (pin "1") (pinfunction "1_1") (pintype "passive"))
    )
    (net (code "96") (name "Net-(LED31-K)") (class "Default")
      (node (ref "LED31") (pin "1") (pinfunction "K_1") (pintype "passive"))
      (node (ref "R141") (pin "2") (pinfunction "2_2") (pintype "passive"))
    )
    (net (code "97") (name "Net-(LED33-A)") (class "Default")
      (node (ref "LED33") (pin "2") (pinfunction "A_2") (pintype "passive"))
      (node (ref "R91") (pin "1") (pinfunction "1_1") (pintype "passive"))
    )
    (net (code "98") (name "Net-(LED33-K)") (class "Default")
      (node (ref "LED33") (pin "1") (pinfunction "K_1") (pintype "passive"))
      (node (ref "R95") (pin "2") (pinfunction "2_2") (pintype "passive"))
    )
    (net (code "99") (name "Net-(LED34-A)") (class "Default")
      (node (ref "LED34") (pin "2") (pinfunction "A_2") (pintype "passive"))
      (node (ref "R92") (pin "1") (pinfunction "1_1") (pintype "passive"))
    )
    (net (code "100") (name "Net-(LED34-K)") (class "Default")
      (node (ref "LED34") (pin "1") (pinfunction "K_1") (pintype "passive"))
      (node (ref "R96") (pin "2") (pinfunction "2_2") (pintype "passive"))
    )
    (net (code "101") (name "Net-(LED36-A)") (class "Default")
      (node (ref "LED36") (pin "2") (pinfunction "A_2") (pintype "passive"))
      (node (ref "R93") (pin "1") (pinfunction "1_1") (pintype "passive"))
    )
    (net (code "102") (name "Net-(LED36-K)") (class "Default")
      (node (ref "LED36") (pin "1") (pinfunction "K_1") (pintype "passive"))
      (node (ref "R97") (pin "2") (pinfunction "2_2") (pintype "passive"))
    )
    (net (code "103") (name "unconnected-(U5-2A1-Pad11)") (class "Default")
      (node (ref "U5") (pin "11") (pinfunction "2A1_11") (pintype "passive+no_connect"))
    )
    (net (code "104") (name "unconnected-(U5-2A2-Pad13)") (class "Default")
      (node (ref "U5") (pin "13") (pinfunction "2A2_13") (pintype "passive+no_connect"))
    )
    (net (code "105") (name "unconnected-(U5-2A3-Pad15)") (class "Default")
      (node (ref "U5") (pin "15") (pinfunction "2A3_15") (pintype "passive+no_connect"))
    )
    (net (code "106") (name "unconnected-(U5-2A4-Pad17)") (class "Default")
      (node (ref "U5") (pin "17") (pinfunction "2A4_17") (pintype "passive+no_connect"))
    )
    (net (code "107") (name "unconnected-(U5-2Y1-Pad9)") (class "Default")
      (node (ref "U5") (pin "9") (pinfunction "2Y1_9") (pintype "passive+no_connect"))
    )
    (net (code "108") (name "unconnected-(U5-2Y2-Pad7)") (class "Default")
      (node (ref "U5") (pin "7") (pinfunction "2Y2_7") (pintype "passive+no_connect"))
    )
    (net (code "109") (name "unconnected-(U5-2Y3-Pad5)") (class "Default")
      (node (ref "U5") (pin "5") (pinfunction "2Y3_5") (pintype "passive+no_connect"))
    )
    (net (code "110") (name "unconnected-(U5-2Y4-Pad3)") (class "Default")
      (node (ref "U5") (pin "3") (pinfunction "2Y4_3") (pintype "passive+no_connect"))
    )
  )
)
